# Connectors_-_Analog.net
KiCad netlist of a schematic drawn in Altium Designer
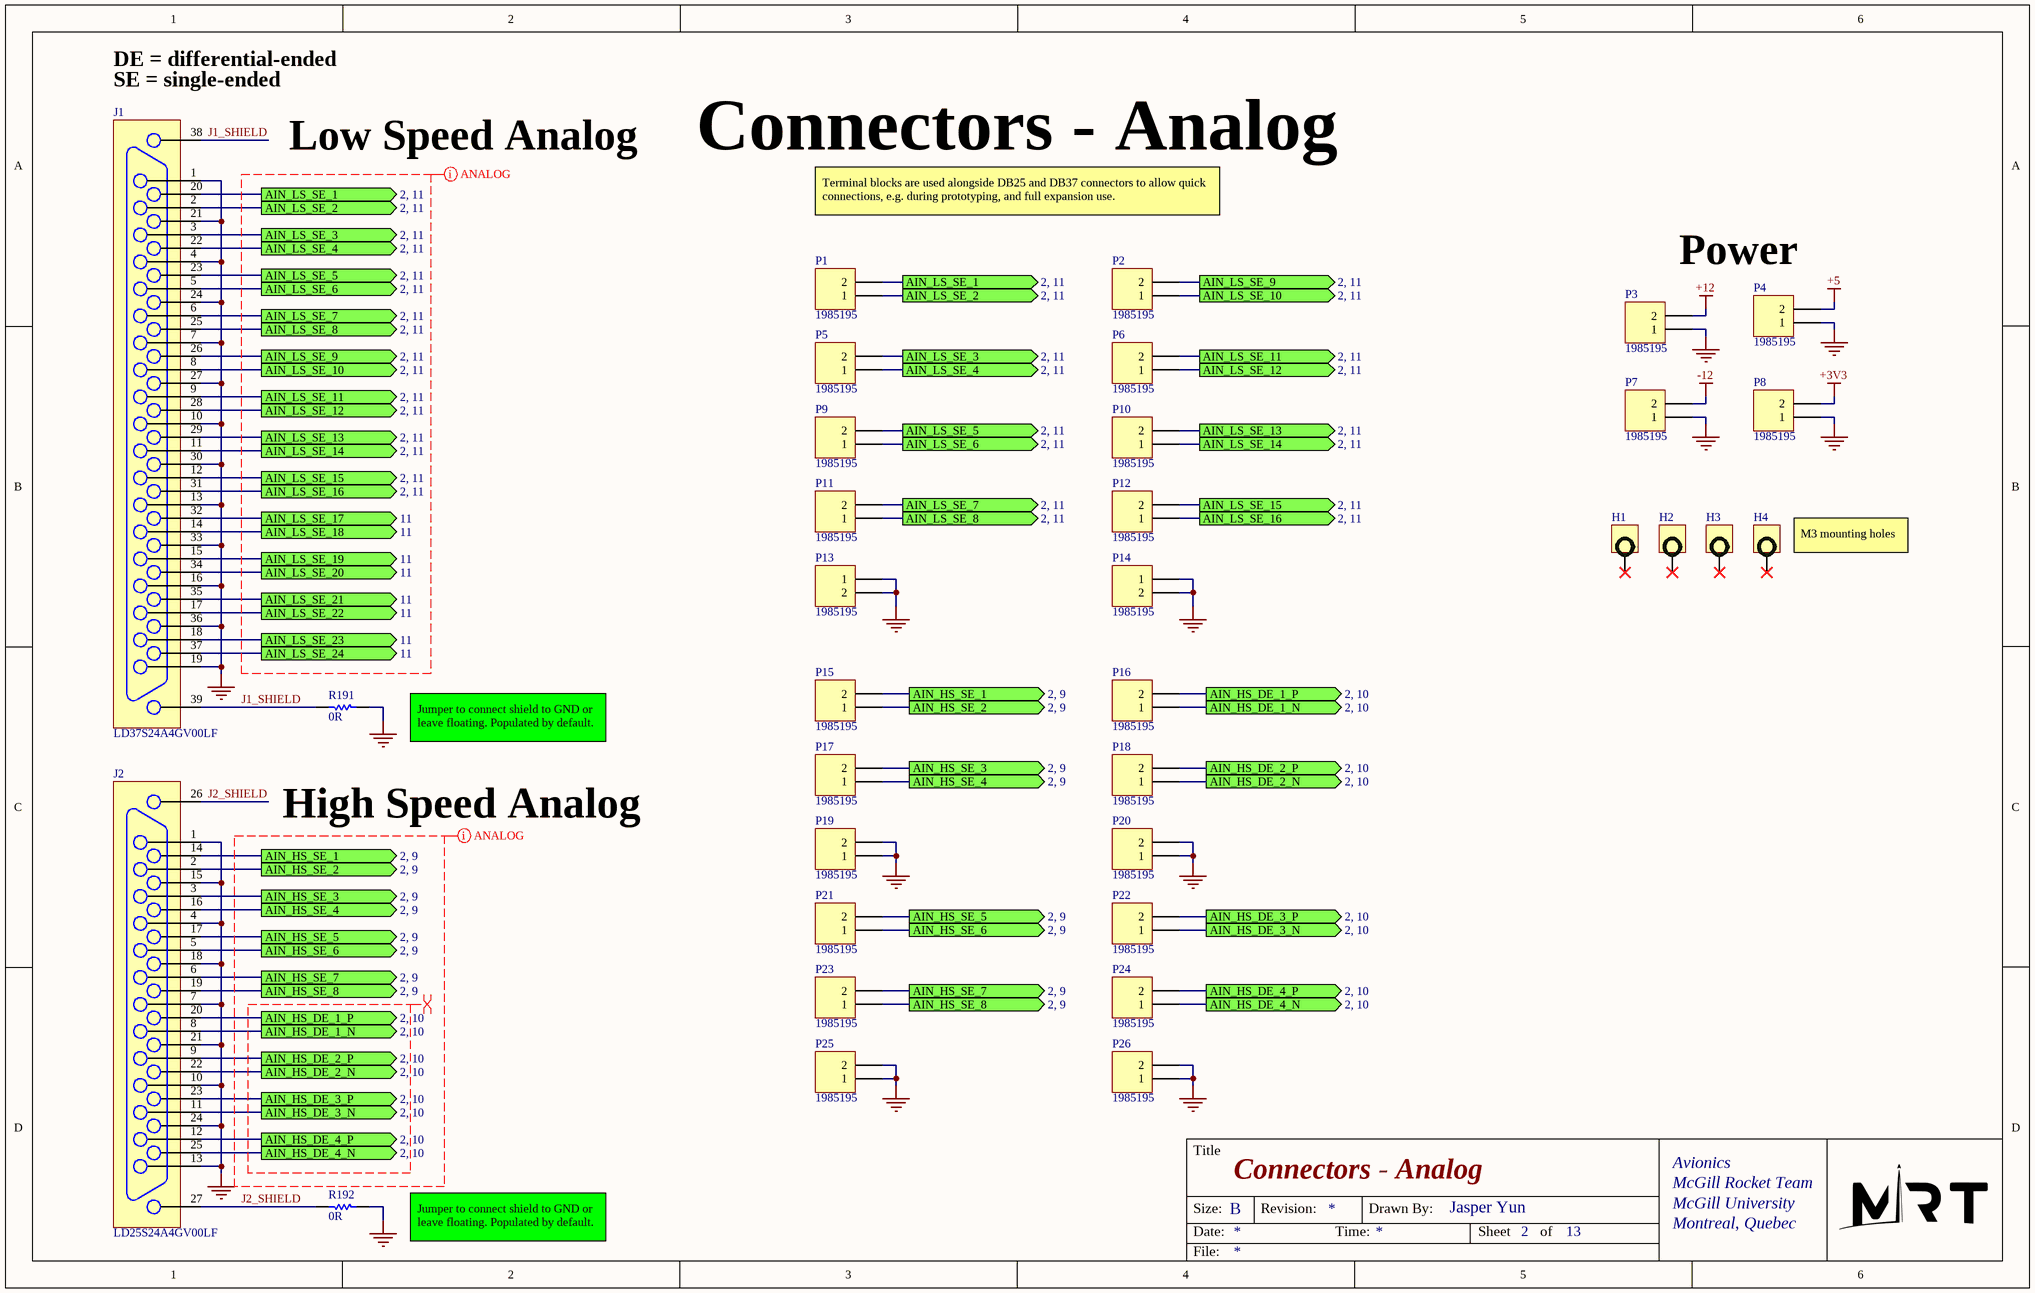
[diagram p0: Connectors - Analog.SchDoc]

(export (version "E")
  (design (tool "Eeschema 10.0.6"))
  (components
    (comp (ref "H1") (value "M3") (footprint "HOLE M3") (libsource (lib "MRT SCH Library") (part "Hole")))
    (comp (ref "H2") (value "M3") (footprint "HOLE M3") (libsource (lib "MRT SCH Library") (part "Hole")))
    (comp (ref "H3") (value "M3") (footprint "HOLE M3") (libsource (lib "MRT SCH Library") (part "Hole")))
    (comp (ref "H4") (value "M3") (footprint "HOLE M3") (libsource (lib "MRT SCH Library") (part "Hole")))
    (comp (ref "J1")
      (value "LD37S24A4GV00LF")
      (footprint "Connector DB37 Vertical LD37S24A4GV00LF")
      (description "DB37 LD37S24A4GV00LF (Amphenol ICC)")
      (libsource (lib "MRT SCH Library") (part "Connector DB37 (LD37S24A4GV00LF)"))
    )
    (comp (ref "J2")
      (value "LD25S24A4GV00LF")
      (footprint "Connector DB25 Vertical LD25S24A4GV00LF")
      (description "DB25 LD25S24A4GV00LF (Amphenol ICC)")
      (libsource (lib "MRT SCH Library") (part "Connector DB25 (LD25S24A4GV00LF)"))
    )
    (comp (ref "P1")
      (value "1985195")
      (footprint "Terminal Block 1985195 2-pos 3.5mm pitch")
      (description "Header, 2-Pin")
      (fields (field (name "PUBLISHER") "Altium Limited"))
      (libsource (lib "Miscellaneous Connectors") (part "Header 2"))
    )
    (comp (ref "P2")
      (value "1985195")
      (footprint "Terminal Block 1985195 2-pos 3.5mm pitch")
      (description "Header, 2-Pin")
      (fields (field (name "PUBLISHER") "Altium Limited"))
      (libsource (lib "Miscellaneous Connectors") (part "Header 2"))
    )
    (comp (ref "P3")
      (value "1985195")
      (footprint "Terminal Block 1985195 2-pos 3.5mm pitch")
      (description "Header, 2-Pin")
      (fields (field (name "PUBLISHER") "Altium Limited"))
      (libsource (lib "Miscellaneous Connectors") (part "Header 2"))
    )
    (comp (ref "P4")
      (value "1985195")
      (footprint "Terminal Block 1985195 2-pos 3.5mm pitch")
      (description "Header, 2-Pin")
      (fields (field (name "PUBLISHER") "Altium Limited"))
      (libsource (lib "Miscellaneous Connectors") (part "Header 2"))
    )
    (comp (ref "P5")
      (value "1985195")
      (footprint "Terminal Block 1985195 2-pos 3.5mm pitch")
      (description "Header, 2-Pin")
      (fields (field (name "PUBLISHER") "Altium Limited"))
      (libsource (lib "Miscellaneous Connectors") (part "Header 2"))
    )
    (comp (ref "P6")
      (value "1985195")
      (footprint "Terminal Block 1985195 2-pos 3.5mm pitch")
      (description "Header, 2-Pin")
      (fields (field (name "PUBLISHER") "Altium Limited"))
      (libsource (lib "Miscellaneous Connectors") (part "Header 2"))
    )
    (comp (ref "P7")
      (value "1985195")
      (footprint "Terminal Block 1985195 2-pos 3.5mm pitch")
      (description "Header, 2-Pin")
      (fields (field (name "PUBLISHER") "Altium Limited"))
      (libsource (lib "Miscellaneous Connectors") (part "Header 2"))
    )
    (comp (ref "P8")
      (value "1985195")
      (footprint "Terminal Block 1985195 2-pos 3.5mm pitch")
      (description "Header, 2-Pin")
      (fields (field (name "PUBLISHER") "Altium Limited"))
      (libsource (lib "Miscellaneous Connectors") (part "Header 2"))
    )
    (comp (ref "P9")
      (value "1985195")
      (footprint "Terminal Block 1985195 2-pos 3.5mm pitch")
      (description "Header, 2-Pin")
      (fields (field (name "PUBLISHER") "Altium Limited"))
      (libsource (lib "Miscellaneous Connectors") (part "Header 2"))
    )
    (comp (ref "P10")
      (value "1985195")
      (footprint "Terminal Block 1985195 2-pos 3.5mm pitch")
      (description "Header, 2-Pin")
      (fields (field (name "PUBLISHER") "Altium Limited"))
      (libsource (lib "Miscellaneous Connectors") (part "Header 2"))
    )
    (comp (ref "P11")
      (value "1985195")
      (footprint "Terminal Block 1985195 2-pos 3.5mm pitch")
      (description "Header, 2-Pin")
      (fields (field (name "PUBLISHER") "Altium Limited"))
      (libsource (lib "Miscellaneous Connectors") (part "Header 2"))
    )
    (comp (ref "P12")
      (value "1985195")
      (footprint "Terminal Block 1985195 2-pos 3.5mm pitch")
      (description "Header, 2-Pin")
      (fields (field (name "PUBLISHER") "Altium Limited"))
      (libsource (lib "Miscellaneous Connectors") (part "Header 2"))
    )
    (comp (ref "P13")
      (value "1985195")
      (footprint "Terminal Block 1985195 2-pos 3.5mm pitch")
      (description "Header, 2-Pin")
      (fields (field (name "PUBLISHER") "Altium Limited"))
      (libsource (lib "") (part "Header 2_1"))
    )
    (comp (ref "P14")
      (value "1985195")
      (footprint "Terminal Block 1985195 2-pos 3.5mm pitch")
      (description "Header, 2-Pin")
      (fields (field (name "PUBLISHER") "Altium Limited"))
      (libsource (lib "") (part "Header 2_1"))
    )
    (comp (ref "P15")
      (value "1985195")
      (footprint "Terminal Block 1985195 2-pos 3.5mm pitch")
      (description "Header, 2-Pin")
      (fields (field (name "PUBLISHER") "Altium Limited"))
      (libsource (lib "Miscellaneous Connectors") (part "Header 2"))
    )
    (comp (ref "P16")
      (value "1985195")
      (footprint "Terminal Block 1985195 2-pos 3.5mm pitch")
      (description "Header, 2-Pin")
      (fields (field (name "PUBLISHER") "Altium Limited"))
      (libsource (lib "Miscellaneous Connectors") (part "Header 2"))
    )
    (comp (ref "P17")
      (value "1985195")
      (footprint "Terminal Block 1985195 2-pos 3.5mm pitch")
      (description "Header, 2-Pin")
      (fields (field (name "PUBLISHER") "Altium Limited"))
      (libsource (lib "Miscellaneous Connectors") (part "Header 2"))
    )
    (comp (ref "P18")
      (value "1985195")
      (footprint "Terminal Block 1985195 2-pos 3.5mm pitch")
      (description "Header, 2-Pin")
      (fields (field (name "PUBLISHER") "Altium Limited"))
      (libsource (lib "Miscellaneous Connectors") (part "Header 2"))
    )
    (comp (ref "P19")
      (value "1985195")
      (footprint "Terminal Block 1985195 2-pos 3.5mm pitch")
      (description "Header, 2-Pin")
      (fields (field (name "PUBLISHER") "Altium Limited"))
      (libsource (lib "Miscellaneous Connectors") (part "Header 2"))
    )
    (comp (ref "P20")
      (value "1985195")
      (footprint "Terminal Block 1985195 2-pos 3.5mm pitch")
      (description "Header, 2-Pin")
      (fields (field (name "PUBLISHER") "Altium Limited"))
      (libsource (lib "Miscellaneous Connectors") (part "Header 2"))
    )
    (comp (ref "P21")
      (value "1985195")
      (footprint "Terminal Block 1985195 2-pos 3.5mm pitch")
      (description "Header, 2-Pin")
      (fields (field (name "PUBLISHER") "Altium Limited"))
      (libsource (lib "Miscellaneous Connectors") (part "Header 2"))
    )
    (comp (ref "P22")
      (value "1985195")
      (footprint "Terminal Block 1985195 2-pos 3.5mm pitch")
      (description "Header, 2-Pin")
      (fields (field (name "PUBLISHER") "Altium Limited"))
      (libsource (lib "Miscellaneous Connectors") (part "Header 2"))
    )
    (comp (ref "P23")
      (value "1985195")
      (footprint "Terminal Block 1985195 2-pos 3.5mm pitch")
      (description "Header, 2-Pin")
      (fields (field (name "PUBLISHER") "Altium Limited"))
      (libsource (lib "Miscellaneous Connectors") (part "Header 2"))
    )
    (comp (ref "P24")
      (value "1985195")
      (footprint "Terminal Block 1985195 2-pos 3.5mm pitch")
      (description "Header, 2-Pin")
      (fields (field (name "PUBLISHER") "Altium Limited"))
      (libsource (lib "Miscellaneous Connectors") (part "Header 2"))
    )
    (comp (ref "P25")
      (value "1985195")
      (footprint "Terminal Block 1985195 2-pos 3.5mm pitch")
      (description "Header, 2-Pin")
      (fields (field (name "PUBLISHER") "Altium Limited"))
      (libsource (lib "Miscellaneous Connectors") (part "Header 2"))
    )
    (comp (ref "P26")
      (value "1985195")
      (footprint "Terminal Block 1985195 2-pos 3.5mm pitch")
      (description "Header, 2-Pin")
      (fields (field (name "PUBLISHER") "Altium Limited"))
      (libsource (lib "Miscellaneous Connectors") (part "Header 2"))
    )
    (comp (ref "R191")
      (value "0R")
      (footprint "0402 RES")
      (description "Resistor")
      (fields (field (name "PUBLISHER") "Altium Limited"))
      (libsource (lib "Miscellaneous Devices") (part "Res1"))
    )
    (comp (ref "R192")
      (value "0R")
      (footprint "0402 RES")
      (description "Resistor")
      (fields (field (name "PUBLISHER") "Altium Limited"))
      (libsource (lib "Miscellaneous Devices") (part "Res1"))
    )
  )
  (nets
    (net (code "1") (name "+3V3") (class "Default")
      (node (ref "P8") (pin "2") (pinfunction "2_2") (pintype "passive"))
    )
    (net (code "2") (name "+5") (class "Default")
      (node (ref "P4") (pin "2") (pinfunction "2_2") (pintype "passive"))
    )
    (net (code "3") (name "+12") (class "Default")
      (node (ref "P3") (pin "2") (pinfunction "2_2") (pintype "passive"))
    )
    (net (code "4") (name "-12") (class "Default")
      (node (ref "P7") (pin "2") (pinfunction "2_2") (pintype "passive"))
    )
    (net (code "5") (name "/AIN_HS_DE_1_N") (class "Default")
      (node (ref "J2") (pin "8") (pinfunction "8_8") (pintype "passive"))
      (node (ref "P16") (pin "1") (pinfunction "1_1") (pintype "passive"))
    )
    (net (code "6") (name "/AIN_HS_DE_1_P") (class "Default")
      (node (ref "J2") (pin "20") (pinfunction "20_20") (pintype "passive"))
      (node (ref "P16") (pin "2") (pinfunction "2_2") (pintype "passive"))
    )
    (net (code "7") (name "/AIN_HS_DE_2_N") (class "Default")
      (node (ref "J2") (pin "22") (pinfunction "22_22") (pintype "passive"))
      (node (ref "P18") (pin "1") (pinfunction "1_1") (pintype "passive"))
    )
    (net (code "8") (name "/AIN_HS_DE_2_P") (class "Default")
      (node (ref "J2") (pin "9") (pinfunction "9_9") (pintype "passive"))
      (node (ref "P18") (pin "2") (pinfunction "2_2") (pintype "passive"))
    )
    (net (code "9") (name "/AIN_HS_DE_3_N") (class "Default")
      (node (ref "J2") (pin "11") (pinfunction "11_11") (pintype "passive"))
      (node (ref "P22") (pin "1") (pinfunction "1_1") (pintype "passive"))
    )
    (net (code "10") (name "/AIN_HS_DE_3_P") (class "Default")
      (node (ref "J2") (pin "23") (pinfunction "23_23") (pintype "passive"))
      (node (ref "P22") (pin "2") (pinfunction "2_2") (pintype "passive"))
    )
    (net (code "11") (name "/AIN_HS_DE_4_N") (class "Default")
      (node (ref "J2") (pin "25") (pinfunction "25_25") (pintype "passive"))
      (node (ref "P24") (pin "1") (pinfunction "1_1") (pintype "passive"))
    )
    (net (code "12") (name "/AIN_HS_DE_4_P") (class "Default")
      (node (ref "J2") (pin "12") (pinfunction "12_12") (pintype "passive"))
      (node (ref "P24") (pin "2") (pinfunction "2_2") (pintype "passive"))
    )
    (net (code "13") (name "/AIN_HS_SE_1") (class "Default")
      (node (ref "J2") (pin "14") (pinfunction "14_14") (pintype "passive"))
      (node (ref "P15") (pin "2") (pinfunction "2_2") (pintype "passive"))
    )
    (net (code "14") (name "/AIN_HS_SE_2") (class "Default")
      (node (ref "J2") (pin "2") (pinfunction "2_2") (pintype "passive"))
      (node (ref "P15") (pin "1") (pinfunction "1_1") (pintype "passive"))
    )
    (net (code "15") (name "/AIN_HS_SE_3") (class "Default")
      (node (ref "J2") (pin "3") (pinfunction "3_3") (pintype "passive"))
      (node (ref "P17") (pin "2") (pinfunction "2_2") (pintype "passive"))
    )
    (net (code "16") (name "/AIN_HS_SE_4") (class "Default")
      (node (ref "J2") (pin "16") (pinfunction "16_16") (pintype "passive"))
      (node (ref "P17") (pin "1") (pinfunction "1_1") (pintype "passive"))
    )
    (net (code "17") (name "/AIN_HS_SE_5") (class "Default")
      (node (ref "J2") (pin "17") (pinfunction "17_17") (pintype "passive"))
      (node (ref "P21") (pin "2") (pinfunction "2_2") (pintype "passive"))
    )
    (net (code "18") (name "/AIN_HS_SE_6") (class "Default")
      (node (ref "J2") (pin "5") (pinfunction "5_5") (pintype "passive"))
      (node (ref "P21") (pin "1") (pinfunction "1_1") (pintype "passive"))
    )
    (net (code "19") (name "/AIN_HS_SE_7") (class "Default")
      (node (ref "J2") (pin "6") (pinfunction "6_6") (pintype "passive"))
      (node (ref "P23") (pin "2") (pinfunction "2_2") (pintype "passive"))
    )
    (net (code "20") (name "/AIN_HS_SE_8") (class "Default")
      (node (ref "J2") (pin "19") (pinfunction "19_19") (pintype "passive"))
      (node (ref "P23") (pin "1") (pinfunction "1_1") (pintype "passive"))
    )
    (net (code "21") (name "/AIN_LS_SE_1") (class "Default")
      (node (ref "J1") (pin "20") (pinfunction "20_20") (pintype "passive"))
      (node (ref "P1") (pin "2") (pinfunction "2_2") (pintype "passive"))
    )
    (net (code "22") (name "/AIN_LS_SE_2") (class "Default")
      (node (ref "J1") (pin "2") (pinfunction "2_2") (pintype "passive"))
      (node (ref "P1") (pin "1") (pinfunction "1_1") (pintype "passive"))
    )
    (net (code "23") (name "/AIN_LS_SE_3") (class "Default")
      (node (ref "J1") (pin "3") (pinfunction "3_3") (pintype "passive"))
      (node (ref "P5") (pin "2") (pinfunction "2_2") (pintype "passive"))
    )
    (net (code "24") (name "/AIN_LS_SE_4") (class "Default")
      (node (ref "J1") (pin "22") (pinfunction "22_22") (pintype "passive"))
      (node (ref "P5") (pin "1") (pinfunction "1_1") (pintype "passive"))
    )
    (net (code "25") (name "/AIN_LS_SE_5") (class "Default")
      (node (ref "J1") (pin "23") (pinfunction "23_23") (pintype "passive"))
      (node (ref "P9") (pin "2") (pinfunction "2_2") (pintype "passive"))
    )
    (net (code "26") (name "/AIN_LS_SE_6") (class "Default")
      (node (ref "J1") (pin "5") (pinfunction "5_5") (pintype "passive"))
      (node (ref "P9") (pin "1") (pinfunction "1_1") (pintype "passive"))
    )
    (net (code "27") (name "/AIN_LS_SE_7") (class "Default")
      (node (ref "J1") (pin "6") (pinfunction "6_6") (pintype "passive"))
      (node (ref "P11") (pin "2") (pinfunction "2_2") (pintype "passive"))
    )
    (net (code "28") (name "/AIN_LS_SE_8") (class "Default")
      (node (ref "J1") (pin "25") (pinfunction "25_25") (pintype "passive"))
      (node (ref "P11") (pin "1") (pinfunction "1_1") (pintype "passive"))
    )
    (net (code "29") (name "/AIN_LS_SE_9") (class "Default")
      (node (ref "J1") (pin "26") (pinfunction "26_26") (pintype "passive"))
      (node (ref "P2") (pin "2") (pinfunction "2_2") (pintype "passive"))
    )
    (net (code "30") (name "/AIN_LS_SE_10") (class "Default")
      (node (ref "J1") (pin "8") (pinfunction "8_8") (pintype "passive"))
      (node (ref "P2") (pin "1") (pinfunction "1_1") (pintype "passive"))
    )
    (net (code "31") (name "/AIN_LS_SE_11") (class "Default")
      (node (ref "J1") (pin "9") (pinfunction "9_9") (pintype "passive"))
      (node (ref "P6") (pin "2") (pinfunction "2_2") (pintype "passive"))
    )
    (net (code "32") (name "/AIN_LS_SE_12") (class "Default")
      (node (ref "J1") (pin "28") (pinfunction "28_28") (pintype "passive"))
      (node (ref "P6") (pin "1") (pinfunction "1_1") (pintype "passive"))
    )
    (net (code "33") (name "/AIN_LS_SE_13") (class "Default")
      (node (ref "J1") (pin "29") (pinfunction "29_29") (pintype "passive"))
      (node (ref "P10") (pin "2") (pinfunction "2_2") (pintype "passive"))
    )
    (net (code "34") (name "/AIN_LS_SE_14") (class "Default")
      (node (ref "J1") (pin "11") (pinfunction "11_11") (pintype "passive"))
      (node (ref "P10") (pin "1") (pinfunction "1_1") (pintype "passive"))
    )
    (net (code "35") (name "/AIN_LS_SE_15") (class "Default")
      (node (ref "J1") (pin "12") (pinfunction "12_12") (pintype "passive"))
      (node (ref "P12") (pin "2") (pinfunction "2_2") (pintype "passive"))
    )
    (net (code "36") (name "/AIN_LS_SE_16") (class "Default")
      (node (ref "J1") (pin "31") (pinfunction "31_31") (pintype "passive"))
      (node (ref "P12") (pin "1") (pinfunction "1_1") (pintype "passive"))
    )
    (net (code "37") (name "/AIN_LS_SE_17") (class "Default")
      (node (ref "J1") (pin "32") (pinfunction "32_32") (pintype "passive"))
    )
    (net (code "38") (name "/AIN_LS_SE_18") (class "Default")
      (node (ref "J1") (pin "14") (pinfunction "14_14") (pintype "passive"))
    )
    (net (code "39") (name "/AIN_LS_SE_19") (class "Default")
      (node (ref "J1") (pin "15") (pinfunction "15_15") (pintype "passive"))
    )
    (net (code "40") (name "/AIN_LS_SE_20") (class "Default")
      (node (ref "J1") (pin "34") (pinfunction "34_34") (pintype "passive"))
    )
    (net (code "41") (name "/AIN_LS_SE_21") (class "Default")
      (node (ref "J1") (pin "35") (pinfunction "35_35") (pintype "passive"))
    )
    (net (code "42") (name "/AIN_LS_SE_22") (class "Default")
      (node (ref "J1") (pin "17") (pinfunction "17_17") (pintype "passive"))
    )
    (net (code "43") (name "/AIN_LS_SE_23") (class "Default")
      (node (ref "J1") (pin "18") (pinfunction "18_18") (pintype "passive"))
    )
    (net (code "44") (name "/AIN_LS_SE_24") (class "Default")
      (node (ref "J1") (pin "37") (pinfunction "37_37") (pintype "passive"))
    )
    (net (code "45") (name "/J1_SHIELD") (class "Default")
      (node (ref "J1") (pin "38") (pinfunction "38_38") (pintype "passive"))
      (node (ref "J1") (pin "39") (pinfunction "39_39") (pintype "passive"))
      (node (ref "R191") (pin "1") (pinfunction "1_1") (pintype "passive"))
    )
    (net (code "46") (name "/J2_SHIELD") (class "Default")
      (node (ref "J2") (pin "26") (pinfunction "26_26") (pintype "passive"))
      (node (ref "J2") (pin "27") (pinfunction "27_27") (pintype "passive"))
      (node (ref "R192") (pin "1") (pinfunction "1_1") (pintype "passive"))
    )
    (net (code "47") (name "GND") (class "Default")
      (node (ref "J1") (pin "1") (pinfunction "1_1") (pintype "passive"))
      (node (ref "J1") (pin "10") (pinfunction "10_10") (pintype "passive"))
      (node (ref "J1") (pin "13") (pinfunction "13_13") (pintype "passive"))
      (node (ref "J1") (pin "16") (pinfunction "16_16") (pintype "passive"))
      (node (ref "J1") (pin "19") (pinfunction "19_19") (pintype "passive"))
      (node (ref "J1") (pin "21") (pinfunction "21_21") (pintype "passive"))
      (node (ref "J1") (pin "24") (pinfunction "24_24") (pintype "passive"))
      (node (ref "J1") (pin "27") (pinfunction "27_27") (pintype "passive"))
      (node (ref "J1") (pin "30") (pinfunction "30_30") (pintype "passive"))
      (node (ref "J1") (pin "33") (pinfunction "33_33") (pintype "passive"))
      (node (ref "J1") (pin "36") (pinfunction "36_36") (pintype "passive"))
      (node (ref "J1") (pin "4") (pinfunction "4_4") (pintype "passive"))
      (node (ref "J1") (pin "7") (pinfunction "7_7") (pintype "passive"))
      (node (ref "J2") (pin "1") (pinfunction "1_1") (pintype "passive"))
      (node (ref "J2") (pin "10") (pinfunction "10_10") (pintype "passive"))
      (node (ref "J2") (pin "13") (pinfunction "13_13") (pintype "passive"))
      (node (ref "J2") (pin "15") (pinfunction "15_15") (pintype "passive"))
      (node (ref "J2") (pin "18") (pinfunction "18_18") (pintype "passive"))
      (node (ref "J2") (pin "21") (pinfunction "21_21") (pintype "passive"))
      (node (ref "J2") (pin "24") (pinfunction "24_24") (pintype "passive"))
      (node (ref "J2") (pin "4") (pinfunction "4_4") (pintype "passive"))
      (node (ref "J2") (pin "7") (pinfunction "7_7") (pintype "passive"))
      (node (ref "P13") (pin "1") (pinfunction "1_1") (pintype "passive"))
      (node (ref "P13") (pin "2") (pinfunction "2_2") (pintype "passive"))
      (node (ref "P14") (pin "1") (pinfunction "1_1") (pintype "passive"))
      (node (ref "P14") (pin "2") (pinfunction "2_2") (pintype "passive"))
      (node (ref "P19") (pin "1") (pinfunction "1_1") (pintype "passive"))
      (node (ref "P19") (pin "2") (pinfunction "2_2") (pintype "passive"))
      (node (ref "P20") (pin "1") (pinfunction "1_1") (pintype "passive"))
      (node (ref "P20") (pin "2") (pinfunction "2_2") (pintype "passive"))
      (node (ref "P25") (pin "1") (pinfunction "1_1") (pintype "passive"))
      (node (ref "P25") (pin "2") (pinfunction "2_2") (pintype "passive"))
      (node (ref "P26") (pin "1") (pinfunction "1_1") (pintype "passive"))
      (node (ref "P26") (pin "2") (pinfunction "2_2") (pintype "passive"))
      (node (ref "P3") (pin "1") (pinfunction "1_1") (pintype "passive"))
      (node (ref "P4") (pin "1") (pinfunction "1_1") (pintype "passive"))
      (node (ref "P7") (pin "1") (pinfunction "1_1") (pintype "passive"))
      (node (ref "P8") (pin "1") (pinfunction "1_1") (pintype "passive"))
      (node (ref "R191") (pin "2") (pinfunction "2_2") (pintype "passive"))
      (node (ref "R192") (pin "2") (pinfunction "2_2") (pintype "passive"))
    )
    (net (code "48") (name "unconnected-(H1-TERMINAL-Pad1)") (class "Default")
      (node (ref "H1") (pin "1") (pinfunction "TERMINAL_1") (pintype "passive+no_connect"))
    )
    (net (code "49") (name "unconnected-(H2-TERMINAL-Pad1)") (class "Default")
      (node (ref "H2") (pin "1") (pinfunction "TERMINAL_1") (pintype "passive+no_connect"))
    )
    (net (code "50") (name "unconnected-(H3-TERMINAL-Pad1)") (class "Default")
      (node (ref "H3") (pin "1") (pinfunction "TERMINAL_1") (pintype "passive+no_connect"))
    )
    (net (code "51") (name "unconnected-(H4-TERMINAL-Pad1)") (class "Default")
      (node (ref "H4") (pin "1") (pinfunction "TERMINAL_1") (pintype "passive+no_connect"))
    )
  )
)
